# Smart_4S_and_5S_switchable_BMS_BQ769200.net
KiCad netlist of a schematic drawn in Altium Designer
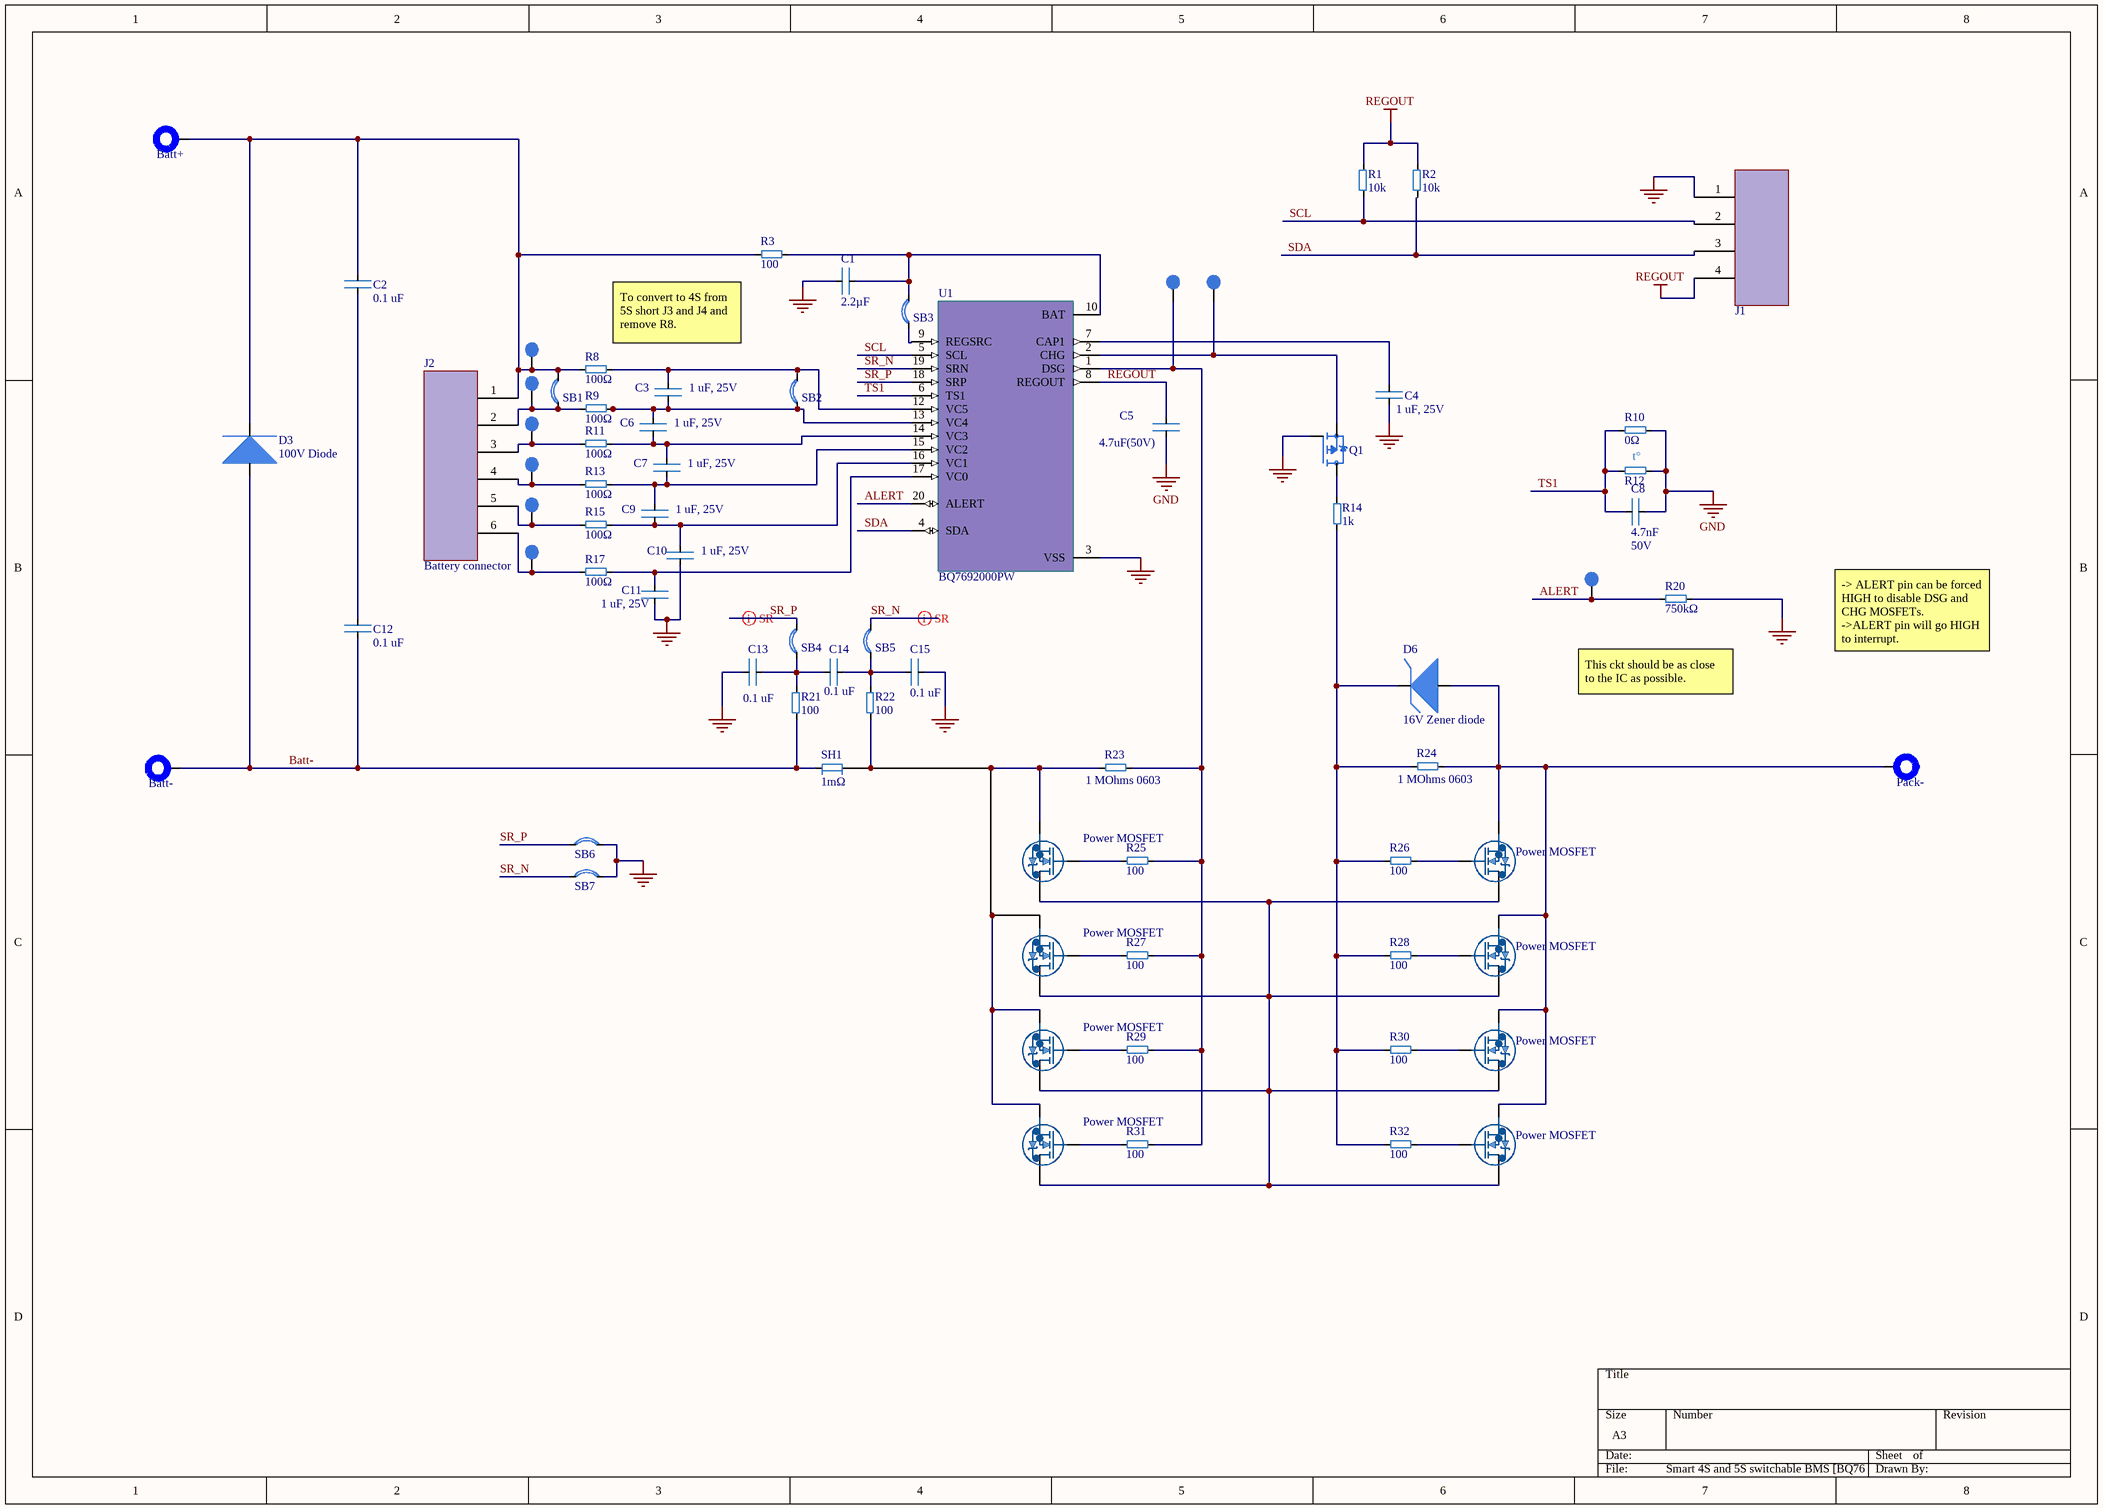
[diagram p0: Smart 4S and 5S switchable BMS [BQ769200].SchDoc]

(export (version "E")
  (design (tool "Eeschema 10.0.6"))
  (components
    (comp (ref "Batt+")
      (value "Power pad")
      (footprint "Power through hole pads")
      (description "Powerplus High Current Terminal")
      (fields
        (field (name "MANUFACTURER") "Wurth Electronics")
        (field (name "MANUFACTURER PART NUMBER") "S93515")
      )
      (libsource (lib "Schlib1") (part "Batt+"))
    )
    (comp (ref "Batt-")
      (value "Power pad")
      (footprint "Power through hole pads")
      (description "Powerplus High Current Terminal")
      (fields
        (field (name "MANUFACTURER") "Wurth Electronics")
        (field (name "MANUFACTURER PART NUMBER") "S93515")
      )
      (libsource (lib "Schlib1") (part "Batt-"))
    )
    (comp (ref "C1")
      (value "2.2µF")
      (footprint "C0805")
      (description "Ceramic Capacitor, Ceramic, 25V, 10% +Tol, 10% -Tol, X7R, 15% TC, 2.2uF, Surface Mount, 0805")
      (fields
        (field (name "MANUFACTURER") "Murata")
        (field (name "MANUFACTURER PART NUMBER") "GCM21BR71E225KA73L")
      )
      (libsource (lib "Schlib1") (part "2.2uF(25V) 0805"))
    )
    (comp (ref "C2")
      (value "0.1 uF")
      (footprint "C0805")
      (fields
        (field (name "MANUFACTURER") "Kyocera AVX")
        (field (name "MANUFACTURER PART NUMBER") "08055C104J4T2A")
      )
      (libsource (lib "BMS Schlib") (part "0.1 uF 0805"))
    )
    (comp (ref "C3")
      (value "1 uF, 25V")
      (footprint "C0805")
      (fields
        (field (name "MANUFACTURER") "Kyocera AVX")
        (field (name "MANUFACTURER PART NUMBER") "08053C105K4Z4A")
      )
      (libsource (lib "Schlib1") (part "1uF 0805"))
    )
    (comp (ref "C4")
      (value "1 uF, 25V")
      (footprint "C0805")
      (fields
        (field (name "MANUFACTURER") "Kyocera AVX")
        (field (name "MANUFACTURER PART NUMBER") "08053C105K4Z4A")
      )
      (libsource (lib "Schlib1") (part "1uF 0805"))
    )
    (comp (ref "C5")
      (value "4.7uF(50V)")
      (footprint "C0805")
      (fields
        (field (name "MANUFACTURER") "Murata")
        (field (name "MANUFACTURER PART NUMBER") "GRM21BR61H475KE51L")
      )
      (libsource (lib "Schlib1") (part "4.7uF(50V) 0805"))
    )
    (comp (ref "C6")
      (value "1 uF, 25V")
      (footprint "C0805")
      (fields
        (field (name "MANUFACTURER") "Kyocera AVX")
        (field (name "MANUFACTURER PART NUMBER") "08053C105K4Z4A")
      )
      (libsource (lib "Schlib1") (part "1uF 0805"))
    )
    (comp (ref "C7")
      (value "1 uF, 25V")
      (footprint "C0805")
      (fields
        (field (name "MANUFACTURER") "Kyocera AVX")
        (field (name "MANUFACTURER PART NUMBER") "08053C105K4Z4A")
      )
      (libsource (lib "Schlib1") (part "1uF 0805"))
    )
    (comp (ref "C8")
      (value "50V")
      (footprint "C0805")
      (description "WCAP-CSGP 0805 (2012Metric) Ceramic Capacitor 0.079Lx0.049W 2.00mmx1.25mm X7R ±10% 4700pF")
      (fields
        (field (name "MANUFACTURER") "Wurth Elektronik")
        (field (name "MANUFACTURER PART NUMBER") "885012207090")
        (field (name "ALTIUM_VALUE") "4.7nF")
      )
      (libsource (lib "Schlib1") (part "4700pF 0805"))
    )
    (comp (ref "C9")
      (value "1 uF, 25V")
      (footprint "C0805")
      (fields
        (field (name "MANUFACTURER") "Kyocera AVX")
        (field (name "MANUFACTURER PART NUMBER") "08053C105K4Z4A")
      )
      (libsource (lib "Schlib1") (part "1uF 0805"))
    )
    (comp (ref "C10")
      (value "1 uF, 25V")
      (footprint "C0805")
      (fields
        (field (name "MANUFACTURER") "Kyocera AVX")
        (field (name "MANUFACTURER PART NUMBER") "08053C105K4Z4A")
      )
      (libsource (lib "Schlib1") (part "1uF 0805"))
    )
    (comp (ref "C11")
      (value "1 uF, 25V")
      (footprint "C0805")
      (fields
        (field (name "MANUFACTURER") "Kyocera AVX")
        (field (name "MANUFACTURER PART NUMBER") "08053C105K4Z4A")
      )
      (libsource (lib "Schlib1") (part "1uF 0805"))
    )
    (comp (ref "C12")
      (value "0.1 uF")
      (footprint "C0805")
      (fields
        (field (name "MANUFACTURER") "Kyocera AVX")
        (field (name "MANUFACTURER PART NUMBER") "08055C104J4T2A")
      )
      (libsource (lib "BMS Schlib") (part "0.1 uF 0805"))
    )
    (comp (ref "C13")
      (value "0.1 uF")
      (footprint "C0805")
      (fields
        (field (name "MANUFACTURER") "Kyocera AVX")
        (field (name "MANUFACTURER PART NUMBER") "08055C104J4T2A")
      )
      (libsource (lib "Schlib1") (part "0.1 uF 0805"))
    )
    (comp (ref "C14")
      (value "0.1 uF")
      (footprint "C0805")
      (fields
        (field (name "MANUFACTURER") "Kyocera AVX")
        (field (name "MANUFACTURER PART NUMBER") "08055C104J4T2A")
      )
      (libsource (lib "Schlib1") (part "0.1 uF 0805"))
    )
    (comp (ref "C15")
      (value "0.1 uF")
      (footprint "C0805")
      (fields
        (field (name "MANUFACTURER") "Kyocera AVX")
        (field (name "MANUFACTURER PART NUMBER") "08055C104J4T2A")
      )
      (libsource (lib "Schlib1") (part "0.1 uF 0805"))
    )
    (comp (ref "D3")
      (value "100V Diode")
      (footprint "Diode 100V")
      (description "Diode Fast Recovery Diode 100V 0.5A 2-Pin TUMD T/R")
      (fields (field (name "MANUFACTURER") "Rohm") (field (name "MANUFACTURER PART NUMBER") "RF05VAM1STR"))
      (libsource (lib "Schlib1") (part "100V Diode"))
    )
    (comp (ref "D6")
      (value "16V Zener diode")
      (footprint "Zener diode 16V")
      (description "Diode Zener Single 16V 5% 500mW Automotive 2-Pin SOD-123 T/R")
      (fields
        (field (name "MANUFACTURER") "ON Semiconductor")
        (field (name "MANUFACTURER PART NUMBER") "SZMMSZ5246BT1G")
      )
      (libsource (lib "Schlib1") (part "16V Zener diode"))
    )
    (comp (ref "J1")
      (value "Headers")
      (footprint "4 pin 2.54mm male header")
      (libsource (lib "Schlib1") (part "I2C port"))
    )
    (comp (ref "J2")
      (value "Battery connector")
      (footprint "6 pin 2.54mm male header")
      (description "WCAP-CSGP 0805 (2012Metric) Ceramic Capacitor 0.079Lx0.049W 2.00mmx1.25mm X7R ±10% 4700pF")
      (fields
        (field (name "MANUFACTURER") "Wurth Elektronik")
        (field (name "MANUFACTURER PART NUMBER") "885012207090")
      )
      (libsource (lib "Schlib1") (part "Battery connector"))
    )
    (comp (ref "Pack-")
      (value "Power pad")
      (footprint "Power through hole pads")
      (description "Powerplus High Current Terminal")
      (fields
        (field (name "MANUFACTURER") "Wurth Electronics")
        (field (name "MANUFACTURER PART NUMBER") "S93515")
      )
      (libsource (lib "Schlib1") (part "Pack-"))
    )
    (comp (ref "Q1")
      (value "200mW")
      (footprint "P-CH 50V 130MA")
      (description "P-Channel 50 V 10 Ohm Enhancement Mode Transistor SOT-323")
      (fields
        (field (name "MANUFACTURER") "Diodes Inc.")
        (field (name "MANUFACTURER PART NUMBER") "BSS84W-7-F")
      )
      (libsource (lib "Schlib1") (part "P-CH 50V 130MA"))
    )
    (comp (ref "Q2")
      (value "Power MOSFET")
      (footprint "GSFP06120")
      (description "Mosfet, N-ch, Single, 120A, 65V,")
      (fields (field (name "MANUFACTURER") "Good-Ark") (field (name "MANUFACTURER PART NUMBER") "GSFP06120"))
      (libsource (lib "BMS Schlib") (part "Power MOSFET"))
    )
    (comp (ref "Q3")
      (value "Power MOSFET")
      (footprint "GSFP06120")
      (description "Mosfet, N-ch, Single, 120A, 65V,")
      (fields (field (name "MANUFACTURER") "Good-Ark") (field (name "MANUFACTURER PART NUMBER") "GSFP06120"))
      (libsource (lib "BMS Schlib") (part "Power MOSFET"))
    )
    (comp (ref "Q4")
      (value "Power MOSFET")
      (footprint "GSFP06120")
      (description "Mosfet, N-ch, Single, 120A, 65V,")
      (fields (field (name "MANUFACTURER") "Good-Ark") (field (name "MANUFACTURER PART NUMBER") "GSFP06120"))
      (libsource (lib "BMS Schlib") (part "Power MOSFET"))
    )
    (comp (ref "Q5")
      (value "Power MOSFET")
      (footprint "GSFP06120")
      (description "Mosfet, N-ch, Single, 120A, 65V,")
      (fields (field (name "MANUFACTURER") "Good-Ark") (field (name "MANUFACTURER PART NUMBER") "GSFP06120"))
      (libsource (lib "BMS Schlib") (part "Power MOSFET"))
    )
    (comp (ref "Q6")
      (value "Power MOSFET")
      (footprint "GSFP06120")
      (description "Mosfet, N-ch, Single, 120A, 65V,")
      (fields (field (name "MANUFACTURER") "Good-Ark") (field (name "MANUFACTURER PART NUMBER") "GSFP06120"))
      (libsource (lib "BMS Schlib") (part "Power MOSFET"))
    )
    (comp (ref "Q7")
      (value "Power MOSFET")
      (footprint "GSFP06120")
      (description "Mosfet, N-ch, Single, 120A, 65V,")
      (fields (field (name "MANUFACTURER") "Good-Ark") (field (name "MANUFACTURER PART NUMBER") "GSFP06120"))
      (libsource (lib "BMS Schlib") (part "Power MOSFET"))
    )
    (comp (ref "Q8")
      (value "Power MOSFET")
      (footprint "GSFP06120")
      (description "Mosfet, N-ch, Single, 120A, 65V,")
      (fields (field (name "MANUFACTURER") "Good-Ark") (field (name "MANUFACTURER PART NUMBER") "GSFP06120"))
      (libsource (lib "BMS Schlib") (part "Power MOSFET"))
    )
    (comp (ref "Q9")
      (value "Power MOSFET")
      (footprint "GSFP06120")
      (description "Mosfet, N-ch, Single, 120A, 65V,")
      (fields (field (name "MANUFACTURER") "Good-Ark") (field (name "MANUFACTURER PART NUMBER") "GSFP06120"))
      (libsource (lib "BMS Schlib") (part "Power MOSFET"))
    )
    (comp (ref "R1")
      (value "10k")
      (footprint "BO_CR0603")
      (fields
        (field (name "MANUFACTURER") "Bourns")
        (field (name "MANUFACTURER PART NUMBER") "CR0603-FX-1002ELF")
        (field (name "TOLERANCE") "1%")
      )
      (libsource (lib "Schlib1") (part "10 kOhms 0603"))
    )
    (comp (ref "R2")
      (value "10k")
      (footprint "BO_CR0603")
      (fields
        (field (name "MANUFACTURER") "Bourns")
        (field (name "MANUFACTURER PART NUMBER") "CR0603-FX-1002ELF")
        (field (name "TOLERANCE") "1%")
      )
      (libsource (lib "Schlib1") (part "10 kOhms 0603"))
    )
    (comp (ref "R3")
      (value "100")
      (footprint "BO_CR0603")
      (fields
        (field (name "MANUFACTURER") "Bourns")
        (field (name "MANUFACTURER PART NUMBER") "CR0603-FX-1000ELF")
        (field (name "TOLERANCE") "1%")
      )
      (libsource (lib "Schlib1") (part "100 Ohms 0603"))
    )
    (comp (ref "R8")
      (value "100Ω")
      (footprint "R1206")
      (description "Res Thick Film 1206 100 Ohm 1% 0.5W(1/2W) ±100ppm/C Pad SMD T/R")
      (fields
        (field (name "MANUFACTURER") "Bourns")
        (field (name "MANUFACTURER PART NUMBER") "CRM1206-FX-1000ELF")
      )
      (libsource (lib "Schlib1") (part "100 Ohms 1206"))
    )
    (comp (ref "R9")
      (value "100Ω")
      (footprint "R1206")
      (description "Res Thick Film 1206 100 Ohm 1% 0.5W(1/2W) ±100ppm/C Pad SMD T/R")
      (fields
        (field (name "MANUFACTURER") "Bourns")
        (field (name "MANUFACTURER PART NUMBER") "CRM1206-FX-1000ELF")
      )
      (libsource (lib "Schlib1") (part "100 Ohms 1206"))
    )
    (comp (ref "R10")
      (value "0Ω")
      (footprint "BO_CR0603")
      (description "Res Metal Plate 0603 0 Ohm Pad SMD T/R Automotive")
      (fields
        (field (name "MANUFACTURER") "Stackpole Electronics")
        (field (name "MANUFACTURER PART NUMBER") "HCJ0603ZT0R00")
      )
      (libsource (lib "Schlib1") (part "0 Ohms 0603"))
    )
    (comp (ref "R11")
      (value "100Ω")
      (footprint "R1206")
      (description "Res Thick Film 1206 100 Ohm 1% 0.5W(1/2W) ±100ppm/C Pad SMD T/R")
      (fields
        (field (name "MANUFACTURER") "Bourns")
        (field (name "MANUFACTURER PART NUMBER") "CRM1206-FX-1000ELF")
      )
      (libsource (lib "Schlib1") (part "100 Ohms 1206"))
    )
    (comp (ref "R12")
      (value "Thermistor")
      (footprint "AT-2_SMI")
      (description "NTC Thermistor, 10000ohm, Through Hole Mount")
      (fields (field (name "MANUFACTURER") "Semitec") (field (name "MANUFACTURER PART NUMBER") "103AT-2"))
      (libsource (lib "Schlib1") (part "10kOhms 103AT-2 NTC Thermistor"))
    )
    (comp (ref "R13")
      (value "100Ω")
      (footprint "R1206")
      (description "Res Thick Film 1206 100 Ohm 1% 0.5W(1/2W) ±100ppm/C Pad SMD T/R")
      (fields
        (field (name "MANUFACTURER") "Bourns")
        (field (name "MANUFACTURER PART NUMBER") "CRM1206-FX-1000ELF")
      )
      (libsource (lib "Schlib1") (part "100 Ohms 1206"))
    )
    (comp (ref "R14")
      (value "1k")
      (footprint "BO_CR0603")
      (fields
        (field (name "MANUFACTURER") "Bourns")
        (field (name "MANUFACTURER PART NUMBER") "CR0603-JW-102ELF")
        (field (name "TOLERANCE") "5%")
      )
      (libsource (lib "Schlib1") (part "1 kOhms 0603"))
    )
    (comp (ref "R15")
      (value "100Ω")
      (footprint "R1206")
      (description "Res Thick Film 1206 100 Ohm 1% 0.5W(1/2W) ±100ppm/C Pad SMD T/R")
      (fields
        (field (name "MANUFACTURER") "Bourns")
        (field (name "MANUFACTURER PART NUMBER") "CRM1206-FX-1000ELF")
      )
      (libsource (lib "Schlib1") (part "100 Ohms 1206"))
    )
    (comp (ref "R17")
      (value "100Ω")
      (footprint "R1206")
      (description "Res Thick Film 1206 100 Ohm 1% 0.5W(1/2W) ±100ppm/C Pad SMD T/R")
      (fields
        (field (name "MANUFACTURER") "Bourns")
        (field (name "MANUFACTURER PART NUMBER") "CRM1206-FX-1000ELF")
      )
      (libsource (lib "Schlib1") (part "100 Ohms 1206"))
    )
    (comp (ref "R20")
      (value "750kΩ")
      (footprint "BO_CR0603")
      (description "Res Thick Film 0603 750K Ohm 1% 1/10W ±100ppm/°C Molded SMD Punched Carrier T/R")
      (fields
        (field (name "MANUFACTURER") "Panasonic")
        (field (name "MANUFACTURER PART NUMBER") "ERJ-3EKF7503V")
      )
      (libsource (lib "Schlib1") (part "750 kOhms 0603"))
    )
    (comp (ref "R21")
      (value "100")
      (footprint "BO_CR0603")
      (fields
        (field (name "MANUFACTURER") "Bourns")
        (field (name "MANUFACTURER PART NUMBER") "CR0603-FX-1000ELF")
        (field (name "TOLERANCE") "1%")
      )
      (libsource (lib "Schlib1") (part "100 Ohms 0603"))
    )
    (comp (ref "R22")
      (value "100")
      (footprint "BO_CR0603")
      (fields
        (field (name "MANUFACTURER") "Bourns")
        (field (name "MANUFACTURER PART NUMBER") "CR0603-FX-1000ELF")
        (field (name "TOLERANCE") "1%")
      )
      (libsource (lib "Schlib1") (part "100 Ohms 0603"))
    )
    (comp (ref "R23")
      (value "1 MOhms 0603")
      (footprint "BO_CR0603")
      (description "Res Thick Film 0603 1M Ohm 1% 1/10W ±100ppm/°C Molded SMD Paper T/R")
      (fields
        (field (name "MANUFACTURER") "Yageo")
        (field (name "MANUFACTURER PART NUMBER") "RC0603FR-071ML")
      )
      (libsource (lib "Schlib1") (part "1 MOhms 0603"))
    )
    (comp (ref "R24")
      (value "1 MOhms 0603")
      (footprint "BO_CR0603")
      (description "Res Thick Film 0603 1M Ohm 1% 1/10W ±100ppm/°C Molded SMD Paper T/R")
      (fields
        (field (name "MANUFACTURER") "Yageo")
        (field (name "MANUFACTURER PART NUMBER") "RC0603FR-071ML")
      )
      (libsource (lib "Schlib1") (part "1 MOhms 0603"))
    )
    (comp (ref "R25")
      (value "100")
      (footprint "BO_CR0603")
      (fields
        (field (name "MANUFACTURER") "Bourns")
        (field (name "MANUFACTURER PART NUMBER") "CR0603-FX-1000ELF")
        (field (name "TOLERANCE") "1%")
      )
      (libsource (lib "Schlib1") (part "100 Ohms 0603"))
    )
    (comp (ref "R26")
      (value "100")
      (footprint "BO_CR0603")
      (fields
        (field (name "MANUFACTURER") "Bourns")
        (field (name "MANUFACTURER PART NUMBER") "CR0603-FX-1000ELF")
        (field (name "TOLERANCE") "1%")
      )
      (libsource (lib "Schlib1") (part "100 Ohms 0603"))
    )
    (comp (ref "R27")
      (value "100")
      (footprint "BO_CR0603")
      (fields
        (field (name "MANUFACTURER") "Bourns")
        (field (name "MANUFACTURER PART NUMBER") "CR0603-FX-1000ELF")
        (field (name "TOLERANCE") "1%")
      )
      (libsource (lib "Schlib1") (part "100 Ohms 0603"))
    )
    (comp (ref "R28")
      (value "100")
      (footprint "BO_CR0603")
      (fields
        (field (name "MANUFACTURER") "Bourns")
        (field (name "MANUFACTURER PART NUMBER") "CR0603-FX-1000ELF")
        (field (name "TOLERANCE") "1%")
      )
      (libsource (lib "Schlib1") (part "100 Ohms 0603"))
    )
    (comp (ref "R29")
      (value "100")
      (footprint "BO_CR0603")
      (fields
        (field (name "MANUFACTURER") "Bourns")
        (field (name "MANUFACTURER PART NUMBER") "CR0603-FX-1000ELF")
        (field (name "TOLERANCE") "1%")
      )
      (libsource (lib "Schlib1") (part "100 Ohms 0603"))
    )
    (comp (ref "R30")
      (value "100")
      (footprint "BO_CR0603")
      (fields
        (field (name "MANUFACTURER") "Bourns")
        (field (name "MANUFACTURER PART NUMBER") "CR0603-FX-1000ELF")
        (field (name "TOLERANCE") "1%")
      )
      (libsource (lib "Schlib1") (part "100 Ohms 0603"))
    )
    (comp (ref "R31")
      (value "100")
      (footprint "BO_CR0603")
      (fields
        (field (name "MANUFACTURER") "Bourns")
        (field (name "MANUFACTURER PART NUMBER") "CR0603-FX-1000ELF")
        (field (name "TOLERANCE") "1%")
      )
      (libsource (lib "Schlib1") (part "100 Ohms 0603"))
    )
    (comp (ref "R32")
      (value "100")
      (footprint "BO_CR0603")
      (fields
        (field (name "MANUFACTURER") "Bourns")
        (field (name "MANUFACTURER PART NUMBER") "CR0603-FX-1000ELF")
        (field (name "TOLERANCE") "1%")
      )
      (libsource (lib "Schlib1") (part "100 Ohms 0603"))
    )
    (comp (ref "SB1")
      (value "Solder bridge")
      (footprint "Solder Bridge")
      (libsource (lib "Schlib1") (part "Solder bridge"))
    )
    (comp (ref "SB2")
      (value "Solder bridge")
      (footprint "Solder Bridge")
      (libsource (lib "Schlib1") (part "Solder bridge"))
    )
    (comp (ref "SB3")
      (value "Solder bridge")
      (footprint "Solder Bridge")
      (libsource (lib "Schlib1") (part "Solder bridge"))
    )
    (comp (ref "SB4")
      (value "Solder bridge")
      (footprint "Solder Bridge")
      (libsource (lib "Schlib1") (part "Solder bridge"))
    )
    (comp (ref "SB5")
      (value "Solder bridge")
      (footprint "Solder Bridge")
      (libsource (lib "Schlib1") (part "Solder bridge"))
    )
    (comp (ref "SB6")
      (value "Solder bridge")
      (footprint "Solder Bridge")
      (libsource (lib "Schlib1") (part "Solder bridge"))
    )
    (comp (ref "SB7")
      (value "Solder bridge")
      (footprint "Solder Bridge")
      (libsource (lib "Schlib1") (part "Solder bridge"))
    )
    (comp (ref "SH1")
      (value "1mΩ")
      (footprint "1mOhms CSR")
      (description "Res Metal Strip 2818 0.001 Ohm 1% 10W ±200ppm/C Pad SMD Automotive T/R")
      (fields
        (field (name "MANUFACTURER") "Vishay")
        (field (name "MANUFACTURER PART NUMBER") "WSHP28181L000FEB")
      )
      (libsource (lib "Schlib1") (part "1mOhms CSR"))
    )
    (comp (ref "TP5") (value "Pad") (footprint "Test Point") (libsource (lib "Schlib1") (part "Test Point")))
    (comp (ref "TP6") (value "Pad") (footprint "Test Point") (libsource (lib "Schlib1") (part "Test Point")))
    (comp (ref "TP7")
      (value "Test Point")
      (footprint "Test Point")
      (libsource (lib "Schlib1") (part "Test Point"))
    )
    (comp (ref "TP9")
      (value "Test Point")
      (footprint "Test Point")
      (libsource (lib "Schlib1") (part "Test Point"))
    )
    (comp (ref "TP11")
      (value "Test Point")
      (footprint "Test Point")
      (libsource (lib "Schlib1") (part "Test Point"))
    )
    (comp (ref "TP13")
      (value "Test Point")
      (footprint "Test Point")
      (libsource (lib "Schlib1") (part "Test Point"))
    )
    (comp (ref "TP15")
      (value "Test Point")
      (footprint "Test Point")
      (libsource (lib "Schlib1") (part "Test Point"))
    )
    (comp (ref "TP17") (value "Pad") (footprint "Test Point") (libsource (lib "Schlib1") (part "Test Point")))
    (comp (ref "TP18")
      (value "Test Point")
      (footprint "Test Point")
      (libsource (lib "Schlib1") (part "Test Point"))
    )
    (comp (ref "U1")
      (value "BQ7692000PW")
      (footprint "BQ7692")
      (description "3 to 5-Series Cell Li-Ion and Li-Phosphate Battery Monitor (bq76940 Family) 20-TSSOP -40 to 85")
      (fields (field (name "MF") "Texas Instruments"))
      (libsource (lib "Schlib1") (part "BQ7692000PW"))
    )
  )
  (nets
    (net (code "1") (name "/ALERT") (class "Default")
      (node (ref "R20") (pin "1") (pinfunction "27_1") (pintype "passive"))
      (node (ref "TP17") (pin "1") (pinfunction "1_1") (pintype "passive"))
      (node (ref "U1") (pin "20") (pinfunction "ALERT_20") (pintype "bidirectional"))
    )
    (net (code "2") (name "/Batt-") (class "Default")
      (node (ref "Batt-") (pin "1") (pinfunction "1_1") (pintype "passive"))
      (node (ref "C12") (pin "1") (pinfunction "26_1") (pintype "passive"))
      (node (ref "D3") (pin "2") (pinfunction "2_2") (pintype "passive"))
      (node (ref "R21") (pin "1") (pinfunction "27_1") (pintype "passive"))
      (node (ref "SH1") (pin "1") (pinfunction "27_1") (pintype "passive"))
    )
    (net (code "3") (name "/SCL") (class "Default")
      (node (ref "J1") (pin "2") (pinfunction "2_2") (pintype "passive"))
      (node (ref "R1") (pin "1") (pinfunction "27_1") (pintype "passive"))
      (node (ref "U1") (pin "5") (pinfunction "SCL_5") (pintype "input"))
    )
    (net (code "4") (name "/SDA") (class "Default")
      (node (ref "J1") (pin "3") (pinfunction "3_3") (pintype "passive"))
      (node (ref "R2") (pin "1") (pinfunction "27_1") (pintype "passive"))
      (node (ref "U1") (pin "4") (pinfunction "SDA_4") (pintype "bidirectional"))
    )
    (net (code "5") (name "/SR_N") (class "Default")
      (node (ref "SB5") (pin "2") (pinfunction "2_2") (pintype "passive"))
      (node (ref "SB7") (pin "1") (pinfunction "1_1") (pintype "passive"))
      (node (ref "U1") (pin "19") (pinfunction "SRN_19") (pintype "input"))
    )
    (net (code "6") (name "/SR_P") (class "Default")
      (node (ref "SB4") (pin "2") (pinfunction "2_2") (pintype "passive"))
      (node (ref "SB6") (pin "1") (pinfunction "1_1") (pintype "passive"))
      (node (ref "U1") (pin "18") (pinfunction "SRP_18") (pintype "input"))
    )
    (net (code "7") (name "/TS1") (class "Default")
      (node (ref "C8") (pin "1") (pinfunction "26_1") (pintype "passive"))
      (node (ref "R10") (pin "1") (pinfunction "27_1") (pintype "passive"))
      (node (ref "R12") (pin "1") (pinfunction "27_1") (pintype "passive"))
      (node (ref "U1") (pin "6") (pinfunction "TS1_6") (pintype "input"))
    )
    (net (code "8") (name "GND") (class "Default")
      (node (ref "C1") (pin "1") (pinfunction "26_1") (pintype "passive"))
      (node (ref "C10") (pin "1") (pinfunction "26_1") (pintype "passive"))
      (node (ref "C11") (pin "1") (pinfunction "26_1") (pintype "passive"))
      (node (ref "C13") (pin "1") (pinfunction "26_1") (pintype "passive"))
      (node (ref "C15") (pin "2") (pinfunction "25_2") (pintype "passive"))
      (node (ref "C4") (pin "1") (pinfunction "26_1") (pintype "passive"))
      (node (ref "C5") (pin "1") (pinfunction "26_1") (pintype "passive"))
      (node (ref "C8") (pin "2") (pinfunction "25_2") (pintype "passive"))
      (node (ref "J1") (pin "1") (pinfunction "1_1") (pintype "passive"))
      (node (ref "Q1") (pin "1") (pinfunction "G_1") (pintype "passive"))
      (node (ref "R10") (pin "2") (pinfunction "28_2") (pintype "passive"))
      (node (ref "R12") (pin "2") (pinfunction "28_2") (pintype "passive"))
      (node (ref "R20") (pin "2") (pinfunction "28_2") (pintype "passive"))
      (node (ref "SB6") (pin "2") (pinfunction "2_2") (pintype "passive"))
      (node (ref "SB7") (pin "2") (pinfunction "2_2") (pintype "passive"))
      (node (ref "U1") (pin "3") (pinfunction "VSS_3") (pintype "power_in"))
    )
    (net (code "9") (name "Net-(C1-25)") (class "Default")
      (node (ref "C1") (pin "2") (pinfunction "25_2") (pintype "passive"))
      (node (ref "R3") (pin "2") (pinfunction "28_2") (pintype "passive"))
      (node (ref "SB3") (pin "2") (pinfunction "2_2") (pintype "passive"))
      (node (ref "U1") (pin "10") (pinfunction "BAT_10") (pintype "power_in"))
    )
    (net (code "10") (name "Net-(C2-25)") (class "Default")
      (node (ref "Batt+") (pin "1") (pinfunction "1_1") (pintype "passive"))
      (node (ref "C2") (pin "2") (pinfunction "25_2") (pintype "passive"))
      (node (ref "D3") (pin "1") (pinfunction "1_1") (pintype "passive"))
      (node (ref "J2") (pin "1") (pinfunction "1_1") (pintype "passive"))
      (node (ref "R3") (pin "1") (pinfunction "27_1") (pintype "passive"))
      (node (ref "R8") (pin "1") (pinfunction "27_1") (pintype "passive"))
      (node (ref "SB1") (pin "2") (pinfunction "2_2") (pintype "passive"))
      (node (ref "TP7") (pin "1") (pinfunction "1_1") (pintype "passive"))
    )
    (net (code "11") (name "Net-(C3-25)") (class "Default")
      (node (ref "C3") (pin "2") (pinfunction "25_2") (pintype "passive"))
      (node (ref "R8") (pin "2") (pinfunction "28_2") (pintype "passive"))
      (node (ref "SB2") (pin "2") (pinfunction "2_2") (pintype "passive"))
      (node (ref "U1") (pin "12") (pinfunction "VC5_12") (pintype "input"))
    )
    (net (code "12") (name "Net-(C3-26)") (class "Default")
      (node (ref "C3") (pin "1") (pinfunction "26_1") (pintype "passive"))
      (node (ref "C6") (pin "2") (pinfunction "25_2") (pintype "passive"))
      (node (ref "R9") (pin "2") (pinfunction "28_2") (pintype "passive"))
      (node (ref "SB2") (pin "1") (pinfunction "1_1") (pintype "passive"))
      (node (ref "U1") (pin "13") (pinfunction "VC4_13") (pintype "input"))
    )
    (net (code "13") (name "Net-(C4-25)") (class "Default")
      (node (ref "C4") (pin "2") (pinfunction "25_2") (pintype "passive"))
      (node (ref "U1") (pin "7") (pinfunction "CAP1_7") (pintype "output"))
    )
    (net (code "14") (name "Net-(C6-26)") (class "Default")
      (node (ref "C6") (pin "1") (pinfunction "26_1") (pintype "passive"))
      (node (ref "C7") (pin "2") (pinfunction "25_2") (pintype "passive"))
      (node (ref "R11") (pin "2") (pinfunction "28_2") (pintype "passive"))
      (node (ref "U1") (pin "14") (pinfunction "VC3_14") (pintype "input"))
    )
    (net (code "15") (name "Net-(C7-26)") (class "Default")
      (node (ref "C7") (pin "1") (pinfunction "26_1") (pintype "passive"))
      (node (ref "C9") (pin "2") (pinfunction "25_2") (pintype "passive"))
      (node (ref "R13") (pin "2") (pinfunction "28_2") (pintype "passive"))
      (node (ref "U1") (pin "15") (pinfunction "VC2_15") (pintype "input"))
    )
    (net (code "16") (name "Net-(C10-25)") (class "Default")
      (node (ref "C10") (pin "2") (pinfunction "25_2") (pintype "passive"))
      (node (ref "C9") (pin "1") (pinfunction "26_1") (pintype "passive"))
      (node (ref "R15") (pin "2") (pinfunction "28_2") (pintype "passive"))
      (node (ref "U1") (pin "16") (pinfunction "VC1_16") (pintype "input"))
    )
    (net (code "17") (name "Net-(C11-25)") (class "Default")
      (node (ref "C11") (pin "2") (pinfunction "25_2") (pintype "passive"))
      (node (ref "R17") (pin "2") (pinfunction "28_2") (pintype "passive"))
      (node (ref "U1") (pin "17") (pinfunction "VC0_17") (pintype "input"))
    )
    (net (code "18") (name "Net-(C12-25)") (class "Default")
      (node (ref "C12") (pin "2") (pinfunction "25_2") (pintype "passive"))
      (node (ref "C2") (pin "1") (pinfunction "26_1") (pintype "passive"))
    )
    (net (code "19") (name "Net-(C13-25)") (class "Default")
      (node (ref "C13") (pin "2") (pinfunction "25_2") (pintype "passive"))
      (node (ref "C14") (pin "1") (pinfunction "26_1") (pintype "passive"))
      (node (ref "R21") (pin "2") (pinfunction "28_2") (pintype "passive"))
      (node (ref "SB4") (pin "1") (pinfunction "1_1") (pintype "passive"))
    )
    (net (code "20") (name "Net-(C14-25)") (class "Default")
      (node (ref "C14") (pin "2") (pinfunction "25_2") (pintype "passive"))
      (node (ref "C15") (pin "1") (pinfunction "26_1") (pintype "passive"))
      (node (ref "R22") (pin "2") (pinfunction "28_2") (pintype "passive"))
      (node (ref "SB5") (pin "1") (pinfunction "1_1") (pintype "passive"))
    )
    (net (code "21") (name "Net-(Q1-D)") (class "Default")
      (node (ref "Q1") (pin "3") (pinfunction "D_3") (pintype "passive"))
      (node (ref "R14") (pin "1") (pinfunction "27_1") (pintype "passive"))
    )
    (net (code "22") (name "Net-(Q1-S)") (class "Default")
      (node (ref "Q1") (pin "2") (pinfunction "S_2") (pintype "passive"))
      (node (ref "TP6") (pin "1") (pinfunction "1_1") (pintype "passive"))
      (node (ref "U1") (pin "2") (pinfunction "CHG_2") (pintype "output"))
    )
    (net (code "23") (name "Net-(Q2-Pad2)") (class "Default")
      (node (ref "Q2") (pin "2") (pinfunction "2_2") (pintype "passive"))
      (node (ref "Q3") (pin "2") (pinfunction "2_2") (pintype "passive"))
      (node (ref "Q4") (pin "2") (pinfunction "2_2") (pintype "passive"))
      (node (ref "Q5") (pin "2") (pinfunction "2_2") (pintype "passive"))
      (node (ref "Q6") (pin "2") (pinfunction "2_2") (pintype "passive"))
      (node (ref "Q7") (pin "2") (pinfunction "2_2") (pintype "passive"))
      (node (ref "Q8") (pin "2") (pinfunction "2_2") (pintype "passive"))
      (node (ref "Q9") (pin "2") (pinfunction "2_2") (pintype "passive"))
    )
    (net (code "24") (name "Net-(R9-27)") (class "Default")
      (node (ref "J2") (pin "2") (pinfunction "2_2") (pintype "passive"))
      (node (ref "R9") (pin "1") (pinfunction "27_1") (pintype "passive"))
      (node (ref "SB1") (pin "1") (pinfunction "1_1") (pintype "passive"))
      (node (ref "TP9") (pin "1") (pinfunction "1_1") (pintype "passive"))
    )
    (net (code "25") (name "Net-(R11-27)") (class "Default")
      (node (ref "J2") (pin "3") (pinfunction "3_3") (pintype "passive"))
      (node (ref "R11") (pin "1") (pinfunction "27_1") (pintype "passive"))
      (node (ref "TP11") (pin "1") (pinfunction "1_1") (pintype "passive"))
    )
    (net (code "26") (name "Net-(R13-27)") (class "Default")
      (node (ref "J2") (pin "4") (pinfunction "4_4") (pintype "passive"))
      (node (ref "R13") (pin "1") (pinfunction "27_1") (pintype "passive"))
      (node (ref "TP13") (pin "1") (pinfunction "1_1") (pintype "passive"))
    )
    (net (code "27") (name "Net-(R14-28)") (class "Default")
      (node (ref "D6") (pin "1") (pinfunction "1_1") (pintype "passive"))
      (node (ref "R14") (pin "2") (pinfunction "28_2") (pintype "passive"))
      (node (ref "R24") (pin "1") (pinfunction "27_1") (pintype "passive"))
      (node (ref "R26") (pin "1") (pinfunction "27_1") (pintype "passive"))
      (node (ref "R28") (pin "1") (pinfunction "27_1") (pintype "passive"))
      (node (ref "R30") (pin "1") (pinfunction "27_1") (pintype "passive"))
      (node (ref "R32") (pin "1") (pinfunction "27_1") (pintype "passive"))
    )
    (net (code "28") (name "Net-(R15-27)") (class "Default")
      (node (ref "J2") (pin "5") (pinfunction "5_5") (pintype "passive"))
      (node (ref "R15") (pin "1") (pinfunction "27_1") (pintype "passive"))
      (node (ref "TP15") (pin "1") (pinfunction "1_1") (pintype "passive"))
    )
    (net (code "29") (name "Net-(R17-27)") (class "Default")
      (node (ref "J2") (pin "6") (pinfunction "6_6") (pintype "passive"))
      (node (ref "R17") (pin "1") (pinfunction "27_1") (pintype "passive"))
      (node (ref "TP18") (pin "1") (pinfunction "1_1") (pintype "passive"))
    )
    (net (code "30") (name "Net-(R22-27)") (class "Default")
      (node (ref "Q2") (pin "3") (pinfunction "3_3") (pintype "passive"))
      (node (ref "Q4") (pin "3") (pinfunction "3_3") (pintype "passive"))
      (node (ref "Q6") (pin "3") (pinfunction "3_3") (pintype "passive"))
      (node (ref "Q8") (pin "3") (pinfunction "3_3") (pintype "passive"))
      (node (ref "R22") (pin "1") (pinfunction "27_1") (pintype "passive"))
      (node (ref "R23") (pin "1") (pinfunction "27_1") (pintype "passive"))
      (node (ref "SH1") (pin "2") (pinfunction "28_2") (pintype "passive"))
    )
    (net (code "31") (name "Net-(R23-28)") (class "Default")
      (node (ref "R23") (pin "2") (pinfunction "28_2") (pintype "passive"))
      (node (ref "R25") (pin "2") (pinfunction "28_2") (pintype "passive"))
      (node (ref "R27") (pin "2") (pinfunction "28_2") (pintype "passive"))
      (node (ref "R29") (pin "2") (pinfunction "28_2") (pintype "passive"))
      (node (ref "R31") (pin "2") (pinfunction "28_2") (pintype "passive"))
      (node (ref "TP5") (pin "1") (pinfunction "1_1") (pintype "passive"))
      (node (ref "U1") (pin "1") (pinfunction "DSG_1") (pintype "output"))
    )
    (net (code "32") (name "Net-(R24-28)") (class "Default")
      (node (ref "D6") (pin "2") (pinfunction "2_2") (pintype "passive"))
      (node (ref "Pack-") (pin "1") (pinfunction "1_1") (pintype "passive"))
      (node (ref "Q3") (pin "3") (pinfunction "3_3") (pintype "passive"))
      (node (ref "Q5") (pin "3") (pinfunction "3_3") (pintype "passive"))
      (node (ref "Q7") (pin "3") (pinfunction "3_3") (pintype "passive"))
      (node (ref "Q9") (pin "3") (pinfunction "3_3") (pintype "passive"))
      (node (ref "R24") (pin "2") (pinfunction "28_2") (pintype "passive"))
    )
    (net (code "33") (name "Net-(R25-27)") (class "Default")
      (node (ref "Q2") (pin "1") (pinfunction "1_1") (pintype "passive"))
      (node (ref "R25") (pin "1") (pinfunction "27_1") (pintype "passive"))
    )
    (net (code "34") (name "Net-(R26-28)") (class "Default")
      (node (ref "Q3") (pin "1") (pinfunction "1_1") (pintype "passive"))
      (node (ref "R26") (pin "2") (pinfunction "28_2") (pintype "passive"))
    )
    (net (code "35") (name "Net-(R27-27)") (class "Default")
      (node (ref "Q4") (pin "1") (pinfunction "1_1") (pintype "passive"))
      (node (ref "R27") (pin "1") (pinfunction "27_1") (pintype "passive"))
    )
    (net (code "36") (name "Net-(R28-28)") (class "Default")
      (node (ref "Q5") (pin "1") (pinfunction "1_1") (pintype "passive"))
      (node (ref "R28") (pin "2") (pinfunction "28_2") (pintype "passive"))
    )
    (net (code "37") (name "Net-(R29-27)") (class "Default")
      (node (ref "Q6") (pin "1") (pinfunction "1_1") (pintype "passive"))
      (node (ref "R29") (pin "1") (pinfunction "27_1") (pintype "passive"))
    )
    (net (code "38") (name "Net-(R30-28)") (class "Default")
      (node (ref "Q7") (pin "1") (pinfunction "1_1") (pintype "passive"))
      (node (ref "R30") (pin "2") (pinfunction "28_2") (pintype "passive"))
    )
    (net (code "39") (name "Net-(R31-27)") (class "Default")
      (node (ref "Q8") (pin "1") (pinfunction "1_1") (pintype "passive"))
      (node (ref "R31") (pin "1") (pinfunction "27_1") (pintype "passive"))
    )
    (net (code "40") (name "Net-(R32-28)") (class "Default")
      (node (ref "Q9") (pin "1") (pinfunction "1_1") (pintype "passive"))
      (node (ref "R32") (pin "2") (pinfunction "28_2") (pintype "passive"))
    )
    (net (code "41") (name "Net-(U1-REGSRC)") (class "Default")
      (node (ref "SB3") (pin "1") (pinfunction "1_1") (pintype "passive"))
      (node (ref "U1") (pin "9") (pinfunction "REGSRC_9") (pintype "input"))
    )
    (net (code "42") (name "REGOUT") (class "Default")
      (node (ref "C5") (pin "2") (pinfunction "25_2") (pintype "passive"))
      (node (ref "J1") (pin "4") (pinfunction "4_4") (pintype "passive"))
      (node (ref "R1") (pin "2") (pinfunction "28_2") (pintype "passive"))
      (node (ref "R2") (pin "2") (pinfunction "28_2") (pintype "passive"))
      (node (ref "U1") (pin "8") (pinfunction "REGOUT_8") (pintype "output"))
    )
  )
)
